# chuck_rev_1.net
KiCad netlist of a schematic drawn in EAGLE
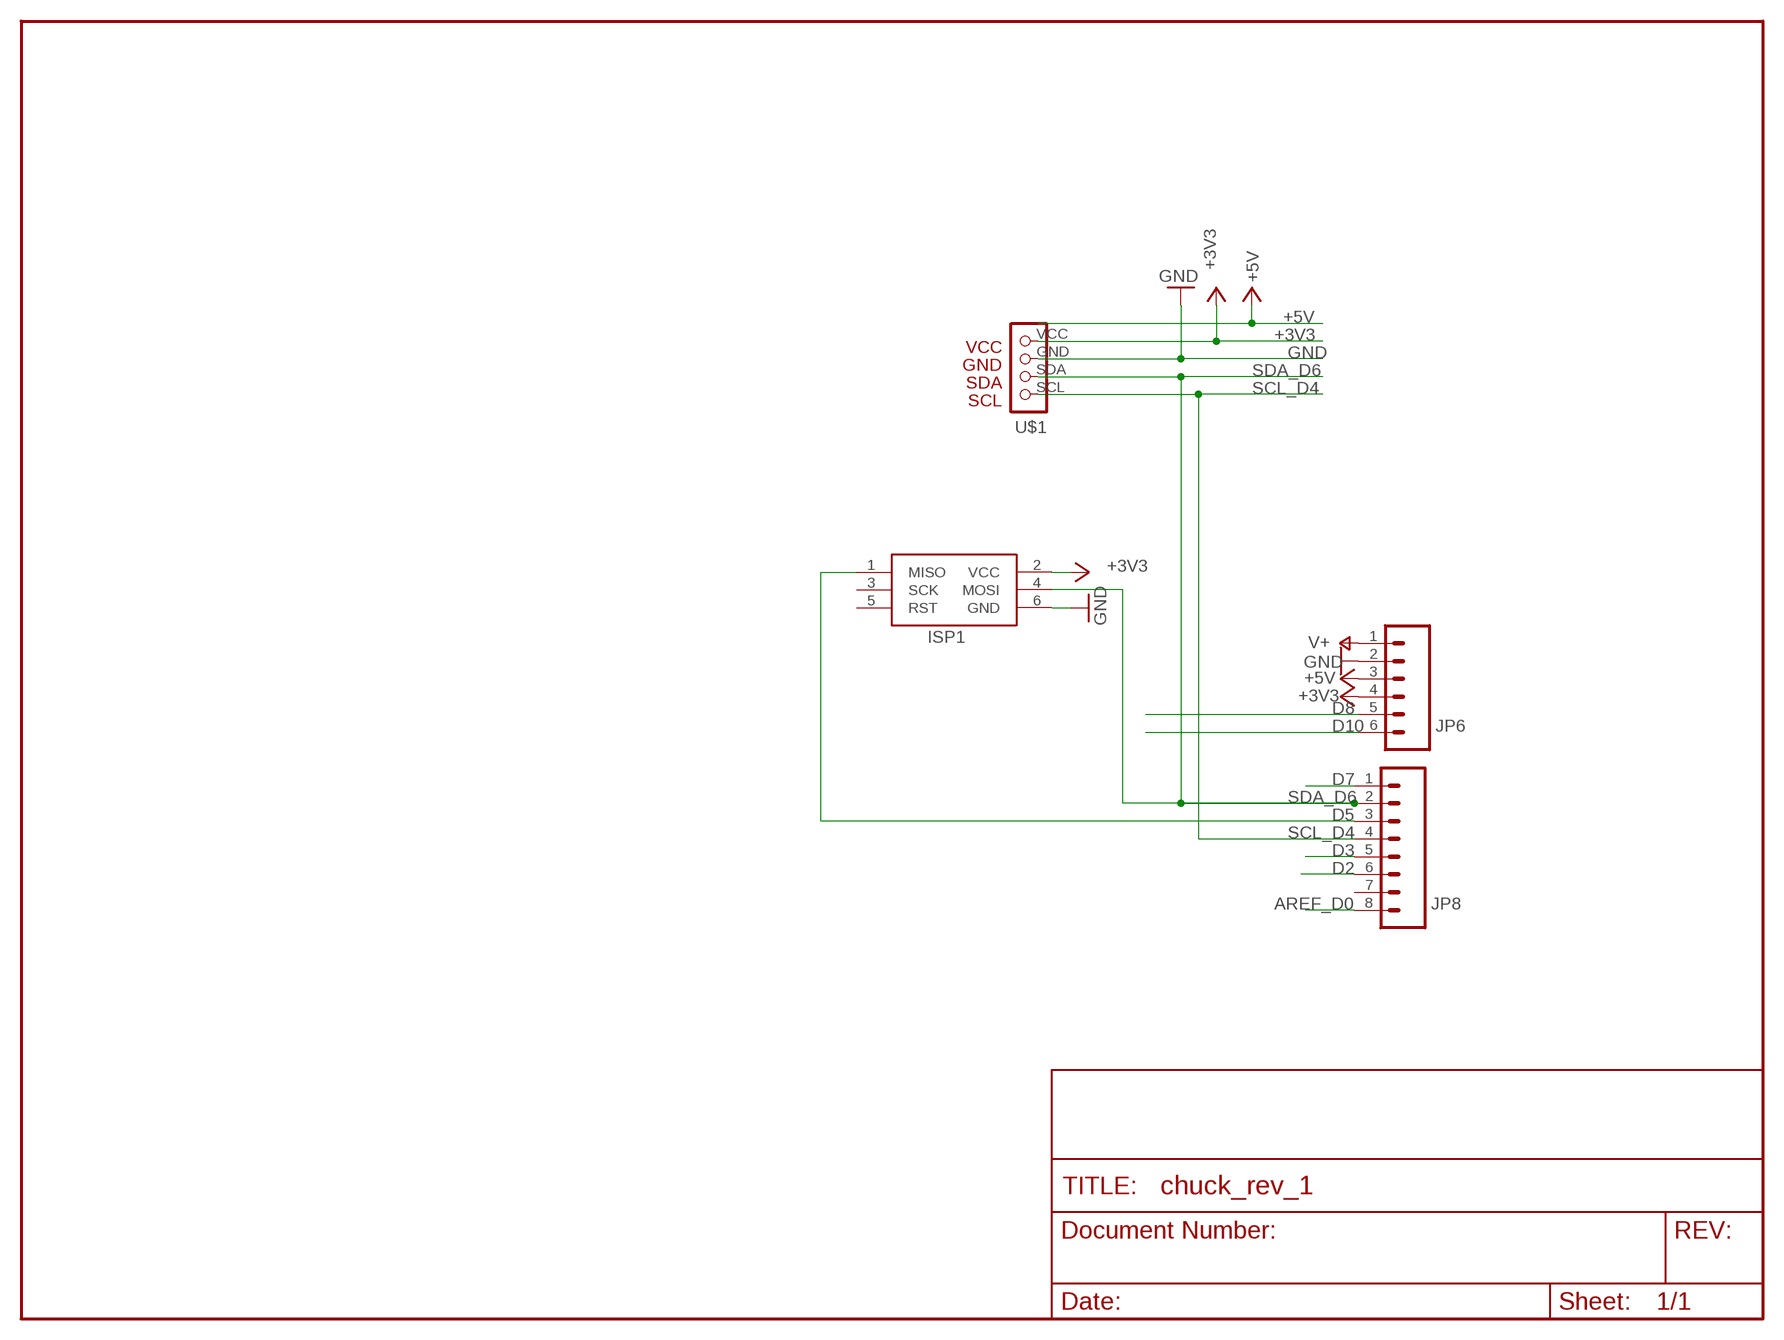
[diagram p0: schematic, sheet 1]

(export (version "E")
  (design (tool "Eeschema 10.0.6"))
  (components
    (comp (ref "ISP1")
      (value "AVRISP-6")
      (footprint "eagle-import:AVRISP")
      (libsource (lib "eagle-import") (part "AVRISP-6"))
    )
    (comp (ref "JP6")
      (value "M06SIP")
      (footprint "eagle-import:1X06")
      (libsource (lib "eagle-import") (part "M06SIP"))
    )
    (comp (ref "JP8")
      (value "M081X08")
      (footprint "eagle-import:1X08")
      (libsource (lib "eagle-import") (part "M081X08"))
    )
    (comp (ref "U$1")
      (value "NUNCHUCKCHUCK")
      (footprint "eagle-import:CONN")
      (libsource (lib "eagle-import") (part "NUNCHUCKCHUCK"))
    )
  )
  (nets
    (net (code "1") (name "+3V3") (class "Default")
      (node (ref "ISP1") (pin "2") (pinfunction "VCC_2") (pintype "power_in"))
      (node (ref "JP6") (pin "4") (pinfunction "4_4") (pintype "passive"))
      (node (ref "U$1") (pin "VCC") (pinfunction "VCC_VCC") (pintype "bidirectional"))
    )
    (net (code "2") (name "+5V") (class "Default")
      (node (ref "JP6") (pin "3") (pinfunction "3_3") (pintype "passive"))
    )
    (net (code "3") (name "/AREF_D0") (class "Default")
      (node (ref "JP8") (pin "8") (pinfunction "8_8") (pintype "passive"))
    )
    (net (code "4") (name "/D2") (class "Default")
      (node (ref "JP8") (pin "6") (pinfunction "6_6") (pintype "passive"))
    )
    (net (code "5") (name "/D3") (class "Default")
      (node (ref "JP8") (pin "5") (pinfunction "5_5") (pintype "passive"))
    )
    (net (code "6") (name "/D5") (class "Default")
      (node (ref "ISP1") (pin "1") (pinfunction "MISO_1") (pintype "input"))
      (node (ref "JP8") (pin "3") (pinfunction "3_3") (pintype "passive"))
    )
    (net (code "7") (name "/D7") (class "Default")
      (node (ref "JP8") (pin "1") (pinfunction "1_1") (pintype "passive"))
    )
    (net (code "8") (name "/D8") (class "Default")
      (node (ref "JP6") (pin "5") (pinfunction "5_5") (pintype "passive"))
    )
    (net (code "9") (name "/D10") (class "Default")
      (node (ref "JP6") (pin "6") (pinfunction "6_6") (pintype "passive"))
    )
    (net (code "10") (name "/SCL_D4") (class "Default")
      (node (ref "JP8") (pin "4") (pinfunction "4_4") (pintype "passive"))
      (node (ref "U$1") (pin "SCL") (pinfunction "SCL_SCL") (pintype "bidirectional"))
    )
    (net (code "11") (name "/SDA_D6") (class "Default")
      (node (ref "ISP1") (pin "4") (pinfunction "MOSI_4") (pintype "output"))
      (node (ref "JP8") (pin "2") (pinfunction "2_2") (pintype "passive"))
      (node (ref "U$1") (pin "SDA") (pinfunction "SDA_SDA") (pintype "bidirectional"))
    )
    (net (code "12") (name "GND") (class "Default")
      (node (ref "ISP1") (pin "6") (pinfunction "GND_6") (pintype "power_in"))
      (node (ref "JP6") (pin "2") (pinfunction "2_2") (pintype "passive"))
      (node (ref "U$1") (pin "GND") (pinfunction "GND_GND") (pintype "bidirectional"))
    )
    (net (code "13") (name "V+") (class "Default")
      (node (ref "JP6") (pin "1") (pinfunction "1_1") (pintype "passive"))
    )
    (net (code "14") (name "unconnected-(ISP1-RST-Pad5)") (class "Default")
      (node (ref "ISP1") (pin "5") (pinfunction "RST_5") (pintype "output"))
    )
    (net (code "15") (name "unconnected-(ISP1-SCK-Pad3)") (class "Default")
      (node (ref "ISP1") (pin "3") (pinfunction "SCK_3") (pintype "output"))
    )
    (net (code "16") (name "unconnected-(JP8-Pad7)") (class "Default")
      (node (ref "JP8") (pin "7") (pinfunction "7_7") (pintype "passive"))
    )
  )
)
